# 01-multimodal-powersupply.net
KiCad netlist of a schematic drawn in Altium Designer
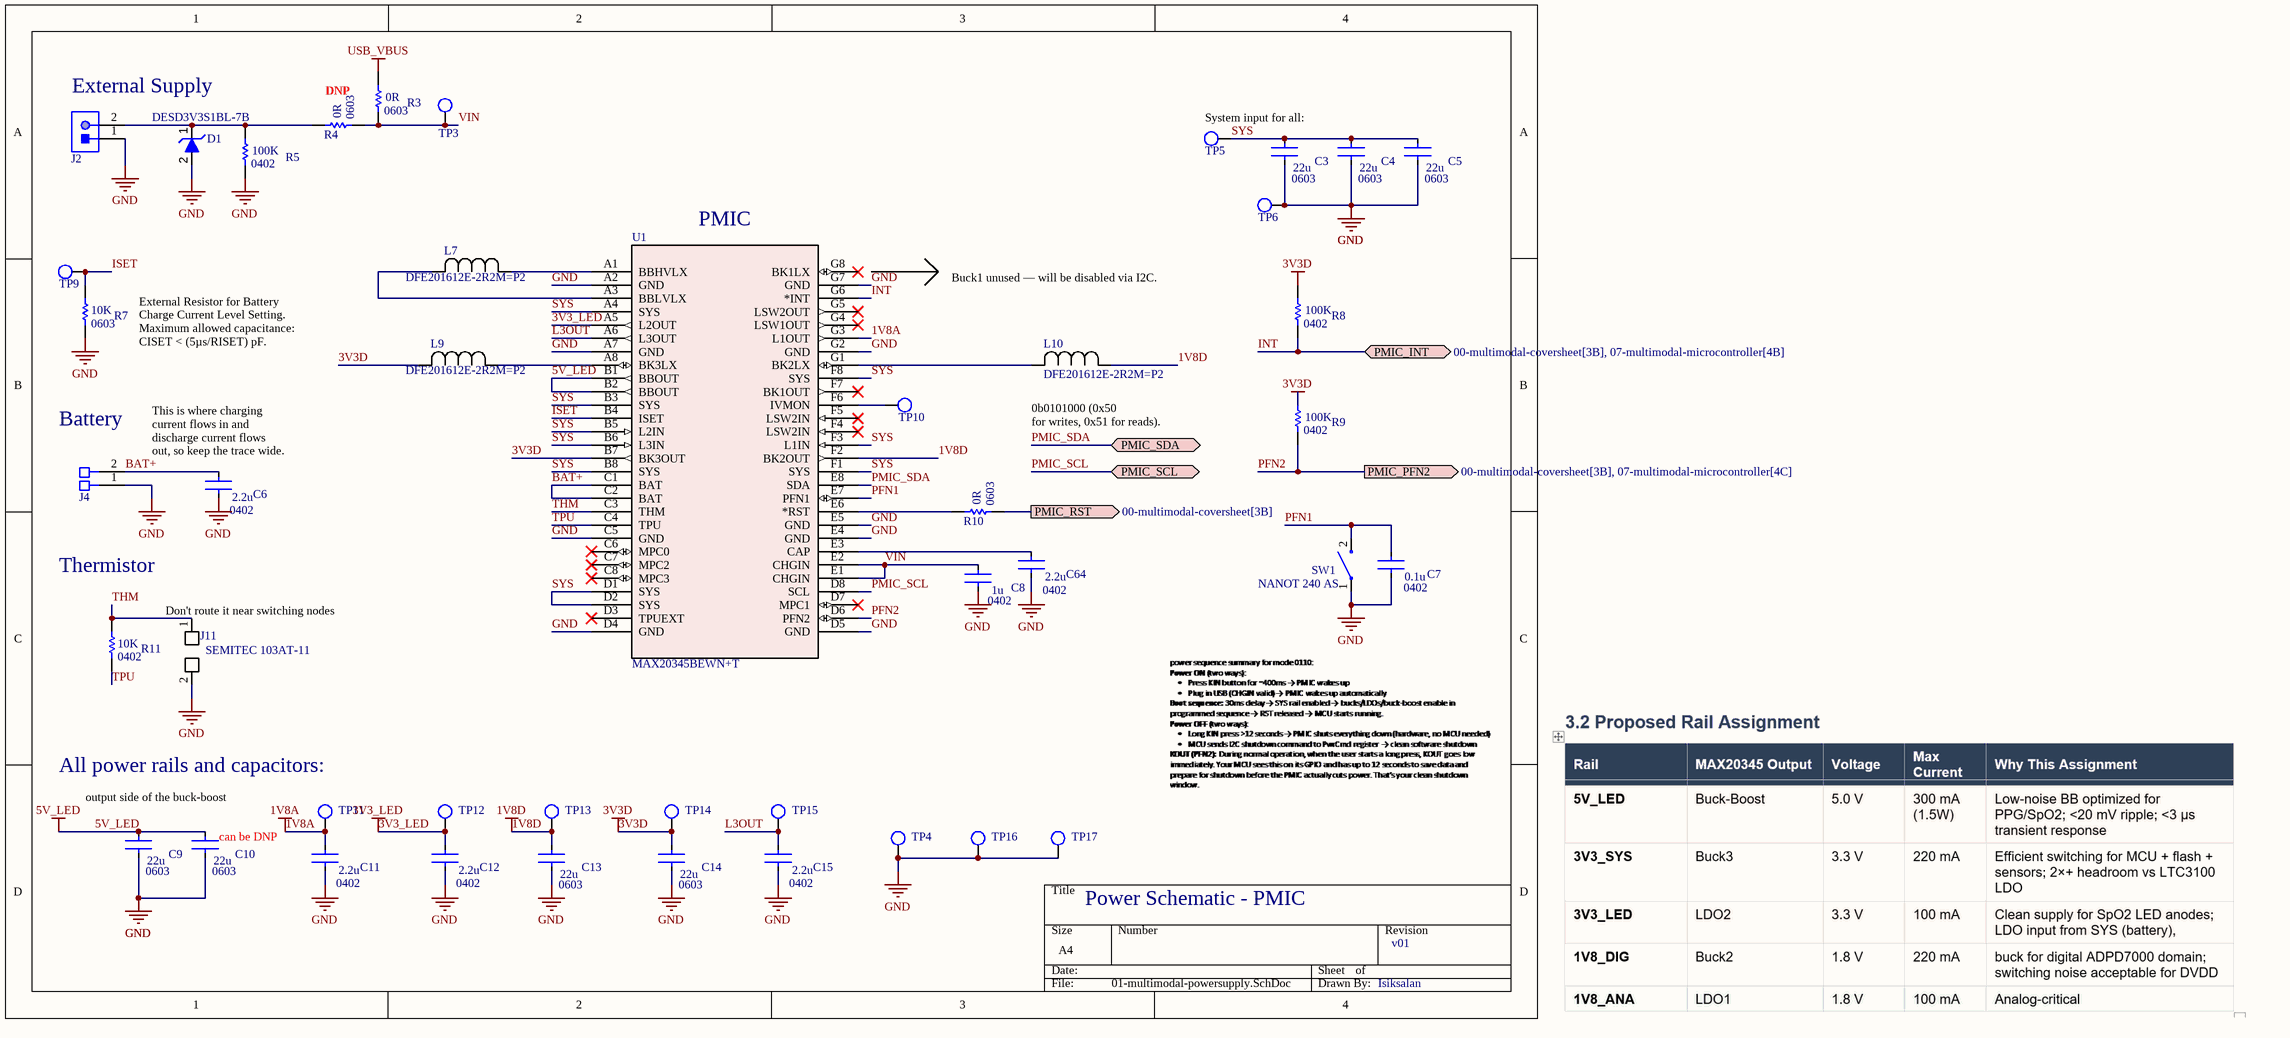
[diagram p0: 01-multimodal-powersupply.SchDoc]

(export (version "E")
  (design (tool "Eeschema 10.0.6"))
  (components
    (comp (ref "C3")
      (value "GRM188R61A226ME15D")
      (footprint "CAPTDK0603")
      (description "CAP CER 22UF 10V X5R 0603")
      (libsource (lib "multimodal") (part "GRM188R61A226ME15D"))
    )
    (comp (ref "C4")
      (value "GRM188R61A226ME15D")
      (footprint "CAPTDK0603")
      (description "CAP CER 22UF 10V X5R 0603")
      (libsource (lib "multimodal") (part "GRM188R61A226ME15D"))
    )
    (comp (ref "C5")
      (value "GRM188R61A226ME15D")
      (footprint "CAPTDK0603")
      (description "CAP CER 22UF 10V X5R 0603")
      (libsource (lib "multimodal") (part "GRM188R61A226ME15D"))
    )
    (comp (ref "C6")
      (value "CL05A225KO5NQNC")
      (footprint "CAPTDK0402")
      (description "CAP CER 2.2UF 16V X5R 0402")
      (libsource (lib "multimodal") (part "CL05A225KO5NQNC"))
    )
    (comp (ref "C7")
      (value "C1005X7R1H104K050BB")
      (footprint "CAPTDK0402")
      (description "CAP CER 0.1UF 50V X7R 0402")
      (libsource (lib "multimodal") (part "C1005X7R1H104K050BB"))
    )
    (comp (ref "C8")
      (value "C1005X5R1V105K050BC")
      (footprint "CAPTDK0402")
      (description "CAP CER 1UF 35V X5R 0402")
      (libsource (lib "multimodal") (part "C1005X5R1V105K050BC"))
    )
    (comp (ref "C9")
      (value "GRM188R61A226ME15D")
      (footprint "CAPTDK0603")
      (description "CAP CER 22UF 10V X5R 0603")
      (libsource (lib "multimodal") (part "GRM188R61A226ME15D"))
    )
    (comp (ref "C10")
      (value "GRM188R61A226ME15D")
      (footprint "CAPTDK0603")
      (description "CAP CER 22UF 10V X5R 0603")
      (libsource (lib "multimodal") (part "GRM188R61A226ME15D"))
    )
    (comp (ref "C11")
      (value "CL05A225KO5NQNC")
      (footprint "CAPTDK0402")
      (description "CAP CER 2.2UF 16V X5R 0402")
      (libsource (lib "multimodal") (part "CL05A225KO5NQNC"))
    )
    (comp (ref "C12")
      (value "CL05A225KO5NQNC")
      (footprint "CAPTDK0402")
      (description "CAP CER 2.2UF 16V X5R 0402")
      (libsource (lib "multimodal") (part "CL05A225KO5NQNC"))
    )
    (comp (ref "C13")
      (value "GRM188R61A226ME15D")
      (footprint "CAPTDK0603")
      (description "CAP CER 22UF 10V X5R 0603")
      (libsource (lib "multimodal") (part "GRM188R61A226ME15D"))
    )
    (comp (ref "C14")
      (value "GRM188R61A226ME15D")
      (footprint "CAPTDK0603")
      (description "CAP CER 22UF 10V X5R 0603")
      (libsource (lib "multimodal") (part "GRM188R61A226ME15D"))
    )
    (comp (ref "C15")
      (value "CL05A225KO5NQNC")
      (footprint "CAPTDK0402")
      (description "CAP CER 2.2UF 16V X5R 0402")
      (libsource (lib "multimodal") (part "CL05A225KO5NQNC"))
    )
    (comp (ref "C64")
      (value "CL05A225KO5NQNC")
      (footprint "CAPTDK0402")
      (description "CAP CER 2.2UF 16V X5R 0402")
      (libsource (lib "multimodal") (part "CL05A225KO5NQNC"))
    )
    (comp (ref "D1")
      (value "DESD3V3S1BL-7B")
      (footprint "TVSDIODE-0402")
      (description "TVS DIODE 3.3V 7V DFN1006-2")
      (fields (field (name "MANUFACTURER") "Diodes"))
      (libsource (lib "multimodal") (part "DESD3V3S1BL-7B"))
    )
    (comp (ref "J2")
      (value "TH-Connector")
      (footprint "2-PIN-TH-CONN")
      (description "Power Connector")
      (libsource (lib "multimodal") (part "TH-Connector"))
    )
    (comp (ref "J4")
      (value "battery_connection")
      (footprint "Battery_connection")
      (libsource (lib "multimodal") (part "battery_connection"))
    )
    (comp (ref "J11")
      (value "SEMITEC 103AT-11")
      (footprint "NTC_connection")
      (description "NTC THERMISTOR 10KOHM 1%")
      (libsource (lib "multimodal") (part "SEMITEC 103AT-11"))
    )
    (comp (ref "L7")
      (value "DFE201612E-2R2M=P2")
      (footprint "IND_DFE2016_MUR-L")
      (description "2.2 µH Shielded Drum Core, Wirewound Inductor 1.8 A 116mOhm Max 0806 (2016 Metric)")
      (fields (field (name "COPYRIGHT") "Copyright (C) 2025 Ultra Librarian. All rights reserved."))
      (libsource (lib "multimodal") (part "DFE201612E-2R2M=P2"))
    )
    (comp (ref "L9")
      (value "DFE201612E-2R2M=P2")
      (footprint "IND_DFE2016_MUR-L")
      (description "2.2 µH Shielded Drum Core, Wirewound Inductor 1.8 A 116mOhm Max 0806 (2016 Metric)")
      (fields (field (name "COPYRIGHT") "Copyright (C) 2025 Ultra Librarian. All rights reserved."))
      (libsource (lib "multimodal") (part "DFE201612E-2R2M=P2"))
    )
    (comp (ref "L10")
      (value "DFE201612E-2R2M=P2")
      (footprint "IND_DFE2016_MUR-L")
      (description "2.2 µH Shielded Drum Core, Wirewound Inductor 1.8 A 116mOhm Max 0806 (2016 Metric)")
      (fields (field (name "COPYRIGHT") "Copyright (C) 2025 Ultra Librarian. All rights reserved."))
      (libsource (lib "multimodal") (part "DFE201612E-2R2M=P2"))
    )
    (comp (ref "R3")
      (value "RMCF0603ZT0R00")
      (footprint "RES-STACK-POLE-0603")
      (description "RES 0 OHM JUMPER 1/10W 0603")
      (libsource (lib "multimodal") (part "RMCF0603ZT0R00"))
    )
    (comp (ref "R4")
      (value "RMCF0603ZT0R00")
      (footprint "RES-STACK-POLE-0603")
      (description "RES 0 OHM JUMPER 1/10W 0603")
      (libsource (lib "multimodal") (part "RMCF0603ZT0R00"))
    )
    (comp (ref "R5")
      (value "RMCF0402FT100K")
      (footprint "RES-STACK-POLE-0402")
      (description "RES 100K OHM 1% 1/16W 0402")
      (libsource (lib "multimodal") (part "RMCF0402FT100K"))
    )
    (comp (ref "R7")
      (value "RMCF0603JG10K0")
      (footprint "RES-STACK-POLE-0603")
      (description "RES 10K OHM 5% 1/10W 0603")
      (libsource (lib "multimodal") (part "RMCF0603JG10K0"))
    )
    (comp (ref "R8")
      (value "RMCF0402FT100K")
      (footprint "RES-STACK-POLE-0402")
      (description "RES 100K OHM 1% 1/16W 0402")
      (libsource (lib "multimodal") (part "RMCF0402FT100K"))
    )
    (comp (ref "R9")
      (value "RMCF0402FT100K")
      (footprint "RES-STACK-POLE-0402")
      (description "RES 100K OHM 1% 1/16W 0402")
      (libsource (lib "multimodal") (part "RMCF0402FT100K"))
    )
    (comp (ref "R10")
      (value "RMCF0603ZT0R00")
      (footprint "RES-STACK-POLE-0603")
      (description "RES 0 OHM JUMPER 1/10W 0603")
      (libsource (lib "multimodal") (part "RMCF0603ZT0R00"))
    )
    (comp (ref "R11")
      (value "RMCF0402FT10K0")
      (footprint "RES-STACK-POLE-0402")
      (description "RES 10K OHM 1% 1/16W 0402")
      (libsource (lib "multimodal") (part "RMCF0402FT10K0"))
    )
    (comp (ref "SW1")
      (value "NANOT 240 AS")
      (footprint "TACTILE-SWITCH - TINY")
      (description "SWITCH TACTILE SPST-NO 0.02A 15V")
      (libsource (lib "multimodal") (part "NANOT 240 AS"))
    )
    (comp (ref "TP3")
      (value "TESTPOINT_S")
      (footprint "TESTPOINT_S")
      (description "Testpoint Surface Pad")
      (libsource (lib "multimodal") (part "TESTPOINT_S"))
    )
    (comp (ref "TP4")
      (value "TESTPOINT_S")
      (footprint "TESTPOINT_S")
      (description "Testpoint Surface Pad")
      (libsource (lib "multimodal") (part "TESTPOINT_S"))
    )
    (comp (ref "TP5")
      (value "TESTPOINT_S")
      (footprint "TESTPOINT_S")
      (description "Testpoint Surface Pad")
      (libsource (lib "multimodal") (part "TESTPOINT_S"))
    )
    (comp (ref "TP6")
      (value "TESTPOINT_S")
      (footprint "TESTPOINT_S")
      (description "Testpoint Surface Pad")
      (libsource (lib "multimodal") (part "TESTPOINT_S"))
    )
    (comp (ref "TP9")
      (value "TESTPOINT_S")
      (footprint "TESTPOINT_S")
      (description "Testpoint Surface Pad")
      (libsource (lib "multimodal") (part "TESTPOINT_S"))
    )
    (comp (ref "TP10")
      (value "TESTPOINT_S")
      (footprint "TESTPOINT_S")
      (description "Testpoint Surface Pad")
      (libsource (lib "multimodal") (part "TESTPOINT_S"))
    )
    (comp (ref "TP11")
      (value "TESTPOINT_S")
      (footprint "TESTPOINT_S")
      (description "Testpoint Surface Pad")
      (libsource (lib "multimodal") (part "TESTPOINT_S"))
    )
    (comp (ref "TP12")
      (value "TESTPOINT_S")
      (footprint "TESTPOINT_S")
      (description "Testpoint Surface Pad")
      (libsource (lib "multimodal") (part "TESTPOINT_S"))
    )
    (comp (ref "TP13")
      (value "TESTPOINT_S")
      (footprint "TESTPOINT_S")
      (description "Testpoint Surface Pad")
      (libsource (lib "multimodal") (part "TESTPOINT_S"))
    )
    (comp (ref "TP14")
      (value "TESTPOINT_S")
      (footprint "TESTPOINT_S")
      (description "Testpoint Surface Pad")
      (libsource (lib "multimodal") (part "TESTPOINT_S"))
    )
    (comp (ref "TP15")
      (value "TESTPOINT_S")
      (footprint "TESTPOINT_S")
      (description "Testpoint Surface Pad")
      (libsource (lib "multimodal") (part "TESTPOINT_S"))
    )
    (comp (ref "TP16")
      (value "TESTPOINT_S")
      (footprint "TESTPOINT_S")
      (description "Testpoint Surface Pad")
      (libsource (lib "multimodal") (part "TESTPOINT_S"))
    )
    (comp (ref "TP17")
      (value "TESTPOINT_S")
      (footprint "TESTPOINT_S")
      (description "Testpoint Surface Pad")
      (libsource (lib "multimodal") (part "TESTPOINT_S"))
    )
    (comp (ref "U1")
      (value "MAX20345BEWN+T")
      (footprint "21-100260_W563H3+1_ADI")
      (fields
        (field (name "MANUFACTURER_PART_NUMBER") "MAX20345KEWN+T")
        (field (name "COPYRIGHT") "Copyright (C) 2026 Ultra Librarian. All rights reserved.")
      )
      (libsource (lib "multimodal") (part "MAX20345BEWN+T"))
    )
  )
  (nets
    (net (code "1") (name "/BAT+") (class "Default")
      (node (ref "C6") (pin "1") (pinfunction "1_1") (pintype "passive"))
      (node (ref "J4") (pin "2") (pinfunction "2_2") (pintype "passive"))
      (node (ref "U1") (pin "C1") (pinfunction "BAT_C1") (pintype "passive"))
      (node (ref "U1") (pin "C2") (pinfunction "BAT_C2") (pintype "passive"))
    )
    (net (code "2") (name "/INT") (class "Default")
      (node (ref "R8") (pin "1") (pinfunction "1_1") (pintype "passive"))
      (node (ref "U1") (pin "G6") (pinfunction "*INT_G6") (pintype "passive"))
    )
    (net (code "3") (name "/ISET") (class "Default")
      (node (ref "R7") (pin "2") (pinfunction "2_2") (pintype "passive"))
      (node (ref "TP9") (pin "1") (pinfunction "1_1") (pintype "passive"))
      (node (ref "U1") (pin "B4") (pinfunction "ISET_B4") (pintype "passive"))
    )
    (net (code "4") (name "/L3OUT") (class "Default")
      (node (ref "C15") (pin "1") (pinfunction "1_1") (pintype "passive"))
      (node (ref "TP15") (pin "1") (pinfunction "1_1") (pintype "passive"))
      (node (ref "U1") (pin "A6") (pinfunction "L3OUT_A6") (pintype "output"))
    )
    (net (code "5") (name "/PFN1") (class "Default")
      (node (ref "C7") (pin "1") (pinfunction "1_1") (pintype "passive"))
      (node (ref "SW1") (pin "2") (pinfunction "2_2") (pintype "passive"))
      (node (ref "U1") (pin "E7") (pinfunction "PFN1_E7") (pintype "bidirectional"))
    )
    (net (code "6") (name "/PFN2") (class "Default")
      (node (ref "R9") (pin "1") (pinfunction "1_1") (pintype "passive"))
      (node (ref "U1") (pin "D6") (pinfunction "PFN2_D6") (pintype "bidirectional"))
    )
    (net (code "7") (name "/PMIC_RST") (class "Default")
      (node (ref "R10") (pin "1") (pinfunction "1_1") (pintype "passive"))
    )
    (net (code "8") (name "/PMIC_SCL") (class "Default")
      (node (ref "U1") (pin "D8") (pinfunction "SCL_D8") (pintype "passive"))
    )
    (net (code "9") (name "/PMIC_SDA") (class "Default")
      (node (ref "U1") (pin "E8") (pinfunction "SDA_E8") (pintype "passive"))
    )
    (net (code "10") (name "/SYS") (class "Default")
      (node (ref "C3") (pin "1") (pinfunction "1_1") (pintype "passive"))
      (node (ref "C4") (pin "1") (pinfunction "1_1") (pintype "passive"))
      (node (ref "C5") (pin "1") (pinfunction "1_1") (pintype "passive"))
      (node (ref "TP5") (pin "1") (pinfunction "1_1") (pintype "passive"))
      (node (ref "U1") (pin "A4") (pinfunction "SYS_A4") (pintype "passive"))
      (node (ref "U1") (pin "B3") (pinfunction "SYS_B3") (pintype "passive"))
      (node (ref "U1") (pin "B5") (pinfunction "L2IN_B5") (pintype "input"))
      (node (ref "U1") (pin "B6") (pinfunction "L3IN_B6") (pintype "input"))
      (node (ref "U1") (pin "B8") (pinfunction "SYS_B8") (pintype "passive"))
      (node (ref "U1") (pin "D1") (pinfunction "SYS_D1") (pintype "passive"))
      (node (ref "U1") (pin "D2") (pinfunction "SYS_D2") (pintype "passive"))
      (node (ref "U1") (pin "F1") (pinfunction "SYS_F1") (pintype "passive"))
      (node (ref "U1") (pin "F3") (pinfunction "L1IN_F3") (pintype "input"))
      (node (ref "U1") (pin "F8") (pinfunction "SYS_F8") (pintype "passive"))
    )
    (net (code "11") (name "/THM") (class "Default")
      (node (ref "J11") (pin "1") (pinfunction "1_1") (pintype "passive"))
      (node (ref "R11") (pin "2") (pinfunction "2_2") (pintype "passive"))
      (node (ref "U1") (pin "C3") (pinfunction "THM_C3") (pintype "passive"))
    )
    (net (code "12") (name "/TPU") (class "Default")
      (node (ref "R11") (pin "1") (pinfunction "1_1") (pintype "passive"))
      (node (ref "U1") (pin "C4") (pinfunction "TPU_C4") (pintype "passive"))
    )
    (net (code "13") (name "/VIN") (class "Default")
      (node (ref "C8") (pin "1") (pinfunction "1_1") (pintype "passive"))
      (node (ref "R3") (pin "1") (pinfunction "1_1") (pintype "passive"))
      (node (ref "R4") (pin "1") (pinfunction "1_1") (pintype "passive"))
      (node (ref "TP3") (pin "1") (pinfunction "1_1") (pintype "passive"))
      (node (ref "U1") (pin "E1") (pinfunction "CHGIN_E1") (pintype "passive"))
      (node (ref "U1") (pin "E2") (pinfunction "CHGIN_E2") (pintype "passive"))
    )
    (net (code "14") (name "1V8A") (class "Default")
      (node (ref "C11") (pin "1") (pinfunction "1_1") (pintype "passive"))
      (node (ref "TP11") (pin "1") (pinfunction "1_1") (pintype "passive"))
      (node (ref "U1") (pin "G3") (pinfunction "L1OUT_G3") (pintype "output"))
    )
    (net (code "15") (name "1V8D") (class "Default")
      (node (ref "C13") (pin "1") (pinfunction "1_1") (pintype "passive"))
      (node (ref "L10") (pin "1") (pinfunction "1_1") (pintype "passive"))
      (node (ref "TP13") (pin "1") (pinfunction "1_1") (pintype "passive"))
      (node (ref "U1") (pin "F2") (pinfunction "BK2OUT_F2") (pintype "output"))
    )
    (net (code "16") (name "3V3D") (class "Default")
      (node (ref "C14") (pin "1") (pinfunction "1_1") (pintype "passive"))
      (node (ref "L9") (pin "2") (pinfunction "2_2") (pintype "passive"))
      (node (ref "R8") (pin "2") (pinfunction "2_2") (pintype "passive"))
      (node (ref "R9") (pin "2") (pinfunction "2_2") (pintype "passive"))
      (node (ref "TP14") (pin "1") (pinfunction "1_1") (pintype "passive"))
      (node (ref "U1") (pin "B7") (pinfunction "BK3OUT_B7") (pintype "output"))
    )
    (net (code "17") (name "3V3_LED") (class "Default")
      (node (ref "C12") (pin "1") (pinfunction "1_1") (pintype "passive"))
      (node (ref "TP12") (pin "1") (pinfunction "1_1") (pintype "passive"))
      (node (ref "U1") (pin "A5") (pinfunction "L2OUT_A5") (pintype "output"))
    )
    (net (code "18") (name "5V_LED") (class "Default")
      (node (ref "C10") (pin "1") (pinfunction "1_1") (pintype "passive"))
      (node (ref "C9") (pin "1") (pinfunction "1_1") (pintype "passive"))
      (node (ref "U1") (pin "B1") (pinfunction "BBOUT_B1") (pintype "output"))
      (node (ref "U1") (pin "B2") (pinfunction "BBOUT_B2") (pintype "output"))
    )
    (net (code "19") (name "GND") (class "Default")
      (node (ref "C10") (pin "2") (pinfunction "2_2") (pintype "passive"))
      (node (ref "C11") (pin "2") (pinfunction "2_2") (pintype "passive"))
      (node (ref "C12") (pin "2") (pinfunction "2_2") (pintype "passive"))
      (node (ref "C13") (pin "2") (pinfunction "2_2") (pintype "passive"))
      (node (ref "C14") (pin "2") (pinfunction "2_2") (pintype "passive"))
      (node (ref "C15") (pin "2") (pinfunction "2_2") (pintype "passive"))
      (node (ref "C3") (pin "2") (pinfunction "2_2") (pintype "passive"))
      (node (ref "C4") (pin "2") (pinfunction "2_2") (pintype "passive"))
      (node (ref "C5") (pin "2") (pinfunction "2_2") (pintype "passive"))
      (node (ref "C6") (pin "2") (pinfunction "2_2") (pintype "passive"))
      (node (ref "C64") (pin "2") (pinfunction "2_2") (pintype "passive"))
      (node (ref "C7") (pin "2") (pinfunction "2_2") (pintype "passive"))
      (node (ref "C8") (pin "2") (pinfunction "2_2") (pintype "passive"))
      (node (ref "C9") (pin "2") (pinfunction "2_2") (pintype "passive"))
      (node (ref "D1") (pin "2") (pintype "passive"))
      (node (ref "J11") (pin "2") (pinfunction "2_2") (pintype "passive"))
      (node (ref "J2") (pin "1") (pinfunction "1_1") (pintype "passive"))
      (node (ref "J4") (pin "1") (pinfunction "1_1") (pintype "passive"))
      (node (ref "R5") (pin "1") (pinfunction "1_1") (pintype "passive"))
      (node (ref "R7") (pin "1") (pinfunction "1_1") (pintype "passive"))
      (node (ref "SW1") (pin "1") (pinfunction "1_1") (pintype "passive"))
      (node (ref "TP16") (pin "1") (pinfunction "1_1") (pintype "passive"))
      (node (ref "TP17") (pin "1") (pinfunction "1_1") (pintype "passive"))
      (node (ref "TP4") (pin "1") (pinfunction "1_1") (pintype "passive"))
      (node (ref "TP6") (pin "1") (pinfunction "1_1") (pintype "passive"))
      (node (ref "U1") (pin "A2") (pinfunction "GND_A2") (pintype "power_in"))
      (node (ref "U1") (pin "A7") (pinfunction "GND_A7") (pintype "power_in"))
      (node (ref "U1") (pin "C5") (pinfunction "GND_C5") (pintype "power_in"))
      (node (ref "U1") (pin "D4") (pinfunction "GND_D4") (pintype "power_in"))
      (node (ref "U1") (pin "D5") (pinfunction "GND_D5") (pintype "power_in"))
      (node (ref "U1") (pin "E4") (pinfunction "GND_E4") (pintype "power_in"))
      (node (ref "U1") (pin "E5") (pinfunction "GND_E5") (pintype "power_in"))
      (node (ref "U1") (pin "G2") (pinfunction "GND_G2") (pintype "power_in"))
      (node (ref "U1") (pin "G7") (pinfunction "GND_G7") (pintype "power_in"))
    )
    (net (code "20") (name "Net-(D1-Pad1)") (class "Default")
      (node (ref "D1") (pin "1") (pintype "passive"))
      (node (ref "J2") (pin "2") (pinfunction "2_2") (pintype "passive"))
      (node (ref "R4") (pin "2") (pinfunction "2_2") (pintype "passive"))
      (node (ref "R5") (pin "2") (pinfunction "2_2") (pintype "passive"))
    )
    (net (code "21") (name "Net-(U1-*RST)") (class "Default")
      (node (ref "R10") (pin "2") (pinfunction "2_2") (pintype "passive"))
      (node (ref "U1") (pin "E6") (pinfunction "*RST_E6") (pintype "passive"))
    )
    (net (code "22") (name "Net-(U1-BBHVLX)") (class "Default")
      (node (ref "L7") (pin "1") (pinfunction "1_1") (pintype "passive"))
      (node (ref "U1") (pin "A1") (pinfunction "BBHVLX_A1") (pintype "passive"))
    )
    (net (code "23") (name "Net-(U1-BBLVLX)") (class "Default")
      (node (ref "L7") (pin "2") (pinfunction "2_2") (pintype "passive"))
      (node (ref "U1") (pin "A3") (pinfunction "BBLVLX_A3") (pintype "passive"))
    )
    (net (code "24") (name "Net-(U1-BK2LX)") (class "Default")
      (node (ref "L10") (pin "2") (pinfunction "2_2") (pintype "passive"))
      (node (ref "U1") (pin "G1") (pinfunction "BK2LX_G1") (pintype "bidirectional"))
    )
    (net (code "25") (name "Net-(U1-BK3LX)") (class "Default")
      (node (ref "L9") (pin "1") (pinfunction "1_1") (pintype "passive"))
      (node (ref "U1") (pin "A8") (pinfunction "BK3LX_A8") (pintype "bidirectional"))
    )
    (net (code "26") (name "Net-(U1-CAP)") (class "Default")
      (node (ref "C64") (pin "1") (pinfunction "1_1") (pintype "passive"))
      (node (ref "U1") (pin "E3") (pinfunction "CAP_E3") (pintype "passive"))
    )
    (net (code "27") (name "Net-(U1-IVMON)") (class "Default")
      (node (ref "TP10") (pin "1") (pinfunction "1_1") (pintype "passive"))
      (node (ref "U1") (pin "F6") (pinfunction "IVMON_F6") (pintype "passive"))
    )
    (net (code "28") (name "USB_VBUS") (class "Default")
      (node (ref "R3") (pin "2") (pinfunction "2_2") (pintype "passive"))
    )
    (net (code "29") (name "unconnected-(U1-BK1LX-PadG8)") (class "Default")
      (node (ref "U1") (pin "G8") (pinfunction "BK1LX_G8") (pintype "bidirectional+no_connect"))
    )
    (net (code "30") (name "unconnected-(U1-BK1OUT-PadF7)") (class "Default")
      (node (ref "U1") (pin "F7") (pinfunction "BK1OUT_F7") (pintype "output+no_connect"))
    )
    (net (code "31") (name "unconnected-(U1-LSW1OUT-PadG4)") (class "Default")
      (node (ref "U1") (pin "G4") (pinfunction "LSW1OUT_G4") (pintype "output+no_connect"))
    )
    (net (code "32") (name "unconnected-(U1-LSW2IN-PadF4)") (class "Default")
      (node (ref "U1") (pin "F4") (pinfunction "LSW2IN_F4") (pintype "input+no_connect"))
    )
    (net (code "33") (name "unconnected-(U1-LSW2IN-PadF5)") (class "Default")
      (node (ref "U1") (pin "F5") (pinfunction "LSW2IN_F5") (pintype "input+no_connect"))
    )
    (net (code "34") (name "unconnected-(U1-LSW2OUT-PadG5)") (class "Default")
      (node (ref "U1") (pin "G5") (pinfunction "LSW2OUT_G5") (pintype "output+no_connect"))
    )
    (net (code "35") (name "unconnected-(U1-MPC0-PadC6)") (class "Default")
      (node (ref "U1") (pin "C6") (pinfunction "MPC0_C6") (pintype "bidirectional+no_connect"))
    )
    (net (code "36") (name "unconnected-(U1-MPC1-PadD7)") (class "Default")
      (node (ref "U1") (pin "D7") (pinfunction "MPC1_D7") (pintype "bidirectional+no_connect"))
    )
    (net (code "37") (name "unconnected-(U1-MPC2-PadC7)") (class "Default")
      (node (ref "U1") (pin "C7") (pinfunction "MPC2_C7") (pintype "bidirectional+no_connect"))
    )
    (net (code "38") (name "unconnected-(U1-MPC3-PadC8)") (class "Default")
      (node (ref "U1") (pin "C8") (pinfunction "MPC3_C8") (pintype "bidirectional+no_connect"))
    )
    (net (code "39") (name "unconnected-(U1-TPUEXT-PadD3)") (class "Default")
      (node (ref "U1") (pin "D3") (pinfunction "TPUEXT_D3") (pintype "passive+no_connect"))
    )
  )
)
